# Orion_Ground_Base.net
KiCad netlist of a schematic drawn in EAGLE
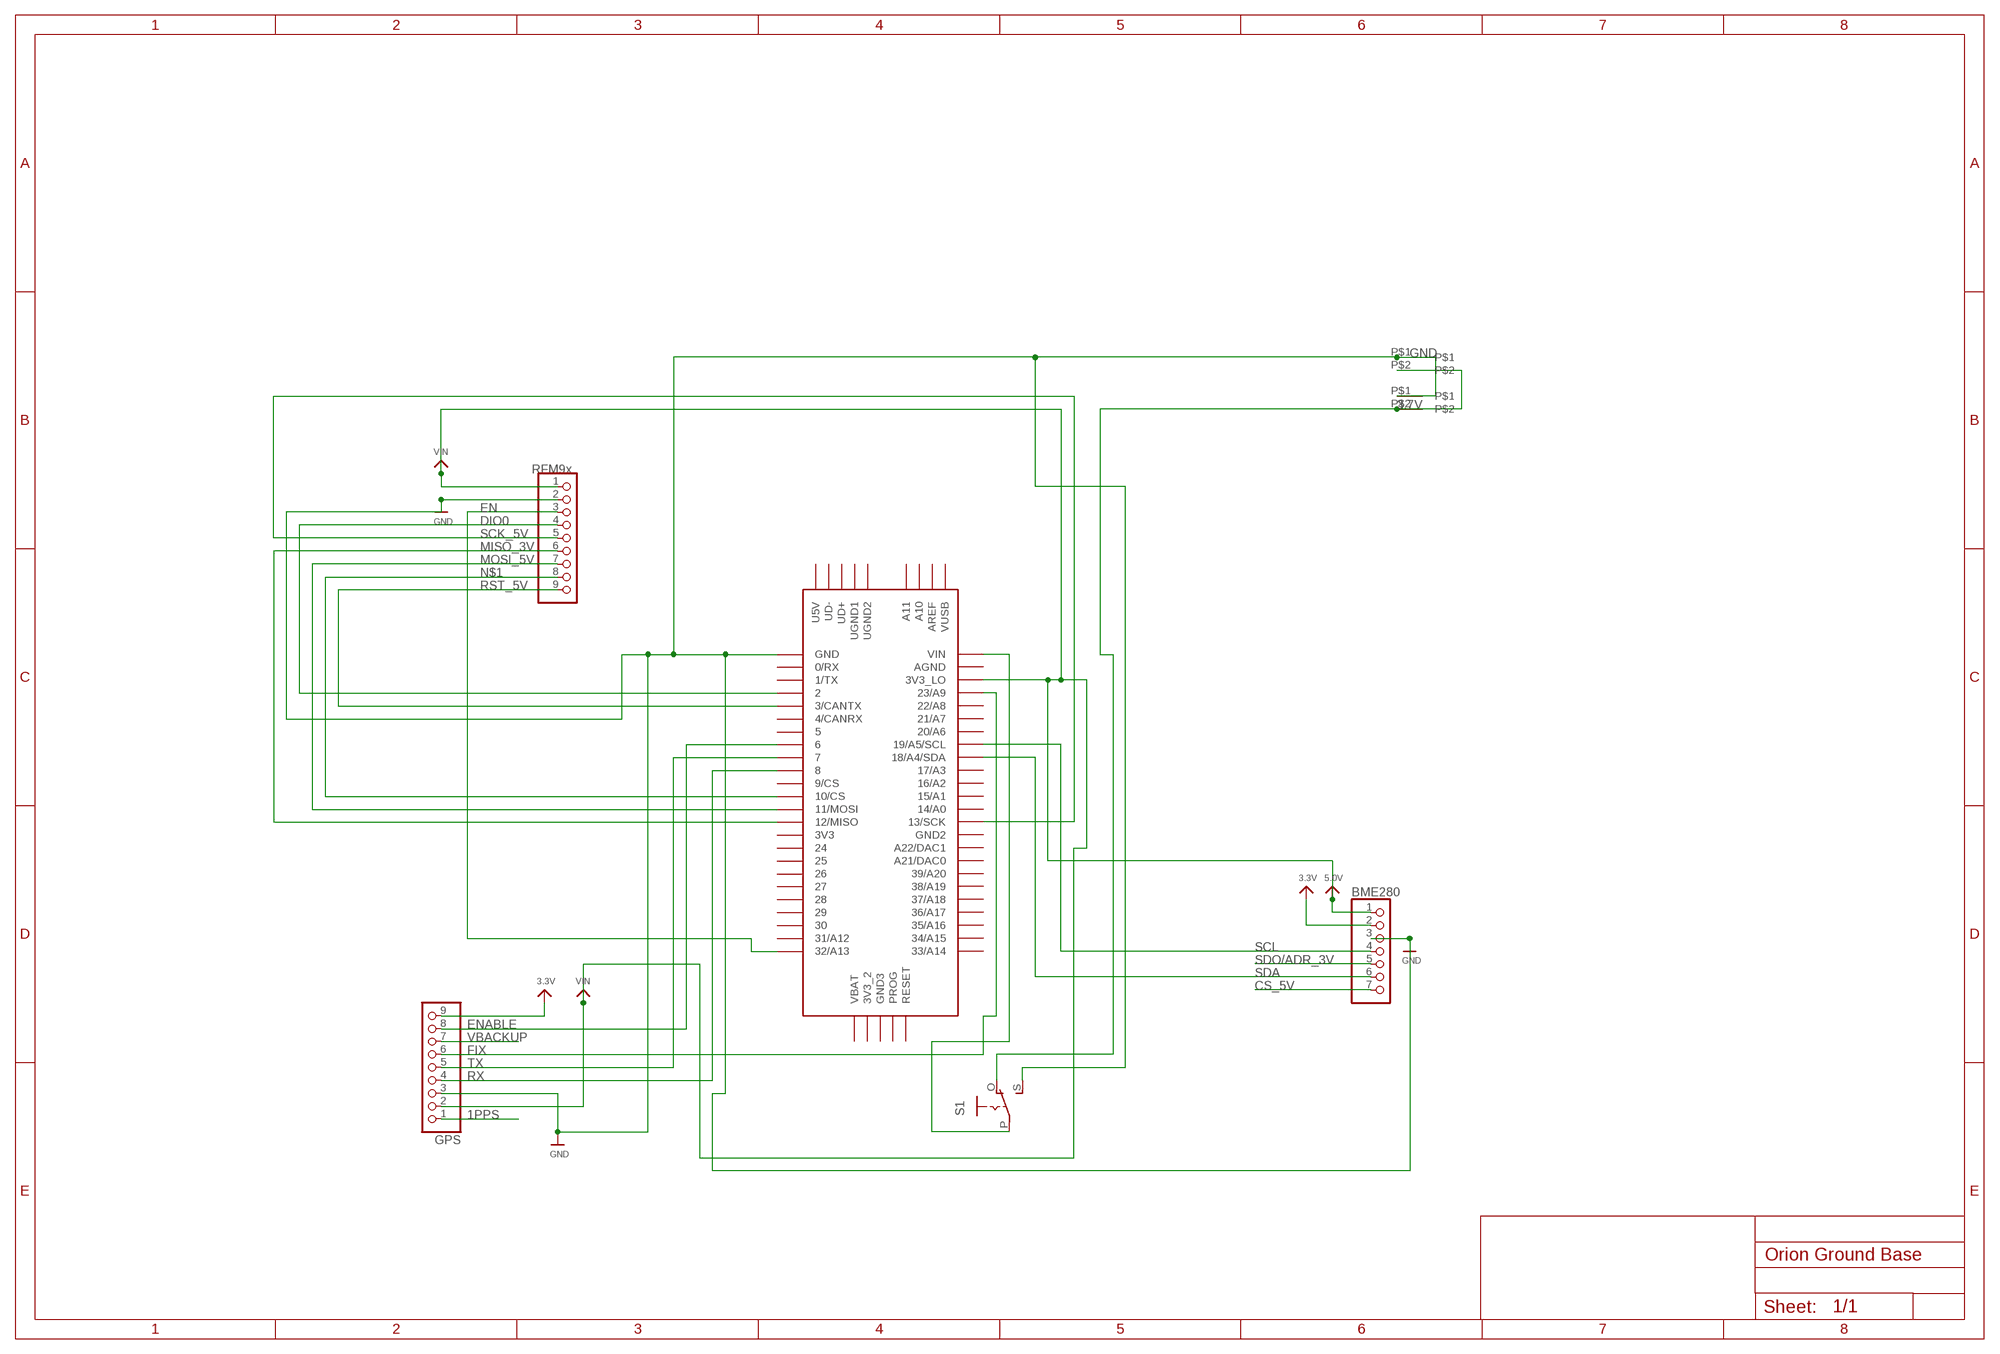
[diagram p0: schematic, sheet 1]

(export (version "E")
  (design (tool "Eeschema 10.0.6"))
  (components
    (comp (ref "BME280")
      (value "HEADER-1X770MIL")
      (footprint "eagle-import:1X07_ROUND_70")
      (libsource (lib "eagle-import") (part "HEADER-1X770MIL"))
    )
    (comp (ref "GPS")
      (value "HEADER-1X970MIL")
      (footprint "eagle-import:1X09_ROUND_70")
      (libsource (lib "eagle-import") (part "HEADER-1X970MIL"))
    )
    (comp (ref "JP3")
      (value "HEADER-1X970MIL")
      (footprint "eagle-import:1X09_ROUND_70")
      (libsource (lib "eagle-import") (part "HEADER-1X970MIL"))
    )
    (comp (ref "S1")
      (value "EG1218S")
      (footprint "eagle-import:EG1218")
      (libsource (lib "eagle-import") (part "EG1218S"))
    )
    (comp (ref "U$1")
      (value "TEENSY_3.5/3.6")
      (footprint "eagle-import:TEENSY_3.5_3.6")
      (libsource (lib "eagle-import") (part "TEENSY_3.5/3.6"))
    )
    (comp (ref "U$7")
      (value "2PINS")
      (footprint "eagle-import:2PINS")
      (libsource (lib "eagle-import") (part "2PINS"))
    )
    (comp (ref "U$8")
      (value "2PINS")
      (footprint "eagle-import:2PINS")
      (libsource (lib "eagle-import") (part "2PINS"))
    )
  )
  (nets
    (net (code "1") (name "/1PPS") (class "Default")
      (node (ref "GPS") (pin "1") (pinfunction "1_1") (pintype "passive"))
    )
    (net (code "2") (name "/CS_5V") (class "Default")
      (node (ref "BME280") (pin "7") (pinfunction "7_7") (pintype "passive"))
    )
    (net (code "3") (name "/DIO0") (class "Default")
      (node (ref "JP3") (pin "4") (pinfunction "4_4") (pintype "passive"))
      (node (ref "U$1") (pin "2") (pinfunction "2_2") (pintype "bidirectional"))
    )
    (net (code "4") (name "/EN") (class "Default")
      (node (ref "JP3") (pin "3") (pinfunction "3_3") (pintype "passive"))
      (node (ref "U$1") (pin "32/A13") (pinfunction "32/A13_32/A13") (pintype "bidirectional"))
    )
    (net (code "5") (name "/ENABLE") (class "Default")
      (node (ref "GPS") (pin "8") (pinfunction "8_8") (pintype "passive"))
      (node (ref "U$1") (pin "6") (pinfunction "6_6") (pintype "bidirectional"))
    )
    (net (code "6") (name "/FIX") (class "Default")
      (node (ref "GPS") (pin "6") (pinfunction "6_6") (pintype "passive"))
      (node (ref "U$1") (pin "23/A9") (pinfunction "23/A9_23/A9") (pintype "bidirectional"))
    )
    (net (code "7") (name "/MISO_3V") (class "Default")
      (node (ref "JP3") (pin "6") (pinfunction "6_6") (pintype "passive"))
      (node (ref "U$1") (pin "12/MISO") (pinfunction "12/MISO_12/MISO") (pintype "bidirectional"))
    )
    (net (code "8") (name "/MOSI_5V") (class "Default")
      (node (ref "JP3") (pin "7") (pinfunction "7_7") (pintype "passive"))
      (node (ref "U$1") (pin "11/MOSI") (pinfunction "11/MOSI_11/MOSI") (pintype "bidirectional"))
    )
    (net (code "9") (name "/N$1") (class "Default")
      (node (ref "JP3") (pin "8") (pinfunction "8_8") (pintype "passive"))
      (node (ref "U$1") (pin "10/CS") (pinfunction "10/CS_10/CS") (pintype "bidirectional"))
    )
    (net (code "10") (name "/RST_5V") (class "Default")
      (node (ref "JP3") (pin "9") (pinfunction "9_9") (pintype "passive"))
      (node (ref "U$1") (pin "3/CANTX") (pinfunction "3/CANTX_3/CANTX") (pintype "bidirectional"))
    )
    (net (code "11") (name "/RX") (class "Default")
      (node (ref "GPS") (pin "4") (pinfunction "4_4") (pintype "passive"))
      (node (ref "U$1") (pin "8") (pinfunction "8_8") (pintype "bidirectional"))
    )
    (net (code "12") (name "/SCK_5V") (class "Default")
      (node (ref "JP3") (pin "5") (pinfunction "5_5") (pintype "passive"))
      (node (ref "U$1") (pin "13/SCK") (pinfunction "13/SCK_13/SCK") (pintype "bidirectional"))
    )
    (net (code "13") (name "/SCL") (class "Default")
      (node (ref "BME280") (pin "4") (pinfunction "4_4") (pintype "passive"))
      (node (ref "U$1") (pin "19/A5/SCL") (pinfunction "19/A5/SCL_19/A5/SCL") (pintype "bidirectional"))
    )
    (net (code "14") (name "/SDA") (class "Default")
      (node (ref "BME280") (pin "6") (pinfunction "6_6") (pintype "passive"))
      (node (ref "U$1") (pin "18/A4/SDA") (pinfunction "18/A4/SDA_18/A4/SDA") (pintype "bidirectional"))
    )
    (net (code "15") (name "/SDO{slash}ADR_3V") (class "Default")
      (node (ref "BME280") (pin "5") (pinfunction "5_5") (pintype "passive"))
    )
    (net (code "16") (name "/TX") (class "Default")
      (node (ref "GPS") (pin "5") (pinfunction "5_5") (pintype "passive"))
      (node (ref "U$1") (pin "7") (pinfunction "7_7") (pintype "bidirectional"))
    )
    (net (code "17") (name "/VBACKUP") (class "Default")
      (node (ref "GPS") (pin "7") (pinfunction "7_7") (pintype "passive"))
    )
    (net (code "18") (name "3.3V") (class "Default")
      (node (ref "BME280") (pin "2") (pinfunction "2_2") (pintype "passive"))
      (node (ref "GPS") (pin "9") (pinfunction "9_9") (pintype "passive"))
    )
    (net (code "19") (name "5.0V") (class "Default")
      (node (ref "BME280") (pin "1") (pinfunction "1_1") (pintype "passive"))
      (node (ref "GPS") (pin "2") (pinfunction "2_2") (pintype "passive"))
      (node (ref "JP3") (pin "1") (pinfunction "1_1") (pintype "passive"))
      (node (ref "U$1") (pin "3V3_LO") (pinfunction "3V3_LO_3V3_LO") (pintype "bidirectional"))
    )
    (net (code "20") (name "GND") (class "Default")
      (node (ref "BME280") (pin "3") (pinfunction "3_3") (pintype "passive"))
      (node (ref "GPS") (pin "3") (pinfunction "3_3") (pintype "passive"))
      (node (ref "JP3") (pin "2") (pinfunction "2_2") (pintype "passive"))
      (node (ref "S1") (pin "S") (pinfunction "S_S") (pintype "passive"))
      (node (ref "U$1") (pin "GND") (pinfunction "GND_GND") (pintype "bidirectional"))
      (node (ref "U$7") (pin "P$1") (pinfunction "P$1_P$1") (pintype "bidirectional"))
      (node (ref "U$8") (pin "P$1") (pinfunction "P$1_P$1") (pintype "bidirectional"))
    )
    (net (code "21") (name "Net-(S1-PadO)") (class "Default")
      (node (ref "S1") (pin "O") (pinfunction "O_O") (pintype "passive"))
      (node (ref "U$7") (pin "P$2") (pinfunction "P$2_P$2") (pintype "bidirectional"))
      (node (ref "U$8") (pin "P$2") (pinfunction "P$2_P$2") (pintype "bidirectional"))
    )
    (net (code "22") (name "Net-(S1-PadP)") (class "Default")
      (node (ref "S1") (pin "P") (pinfunction "P_P") (pintype "passive"))
      (node (ref "U$1") (pin "VIN") (pinfunction "VIN_VIN") (pintype "bidirectional"))
    )
    (net (code "23") (name "unconnected-(U$1-A21{slash}DAC0-Pad21{slash}DAC0)") (class "Default")
      (node (ref "U$1") (pin "21/DAC0") (pinfunction "A21/DAC0_21/DAC0") (pintype "bidirectional"))
    )
    (net (code "24") (name "unconnected-(U$1-Pad0{slash}RX)") (class "Default")
      (node (ref "U$1") (pin "0/RX") (pinfunction "0/RX_0/RX") (pintype "bidirectional"))
    )
    (net (code "25") (name "unconnected-(U$1-Pad1{slash}TX)") (class "Default")
      (node (ref "U$1") (pin "1/TX") (pinfunction "1/TX_1/TX") (pintype "bidirectional"))
    )
    (net (code "26") (name "unconnected-(U$1-Pad3V3)") (class "Default")
      (node (ref "U$1") (pin "3V3") (pinfunction "3V3_3V3") (pintype "bidirectional"))
    )
    (net (code "27") (name "unconnected-(U$1-Pad3V3_2)") (class "Default")
      (node (ref "U$1") (pin "3V3_2") (pinfunction "3V3_2_3V3_2") (pintype "bidirectional"))
    )
    (net (code "28") (name "unconnected-(U$1-Pad4{slash}CANRX)") (class "Default")
      (node (ref "U$1") (pin "4/CANRX") (pinfunction "4/CANRX_4/CANRX") (pintype "bidirectional"))
    )
    (net (code "29") (name "unconnected-(U$1-Pad5)") (class "Default")
      (node (ref "U$1") (pin "5") (pinfunction "5_5") (pintype "bidirectional"))
    )
    (net (code "30") (name "unconnected-(U$1-Pad9{slash}CS)") (class "Default")
      (node (ref "U$1") (pin "9/CS") (pinfunction "9/CS_9/CS") (pintype "bidirectional"))
    )
    (net (code "31") (name "unconnected-(U$1-Pad14{slash}A0)") (class "Default")
      (node (ref "U$1") (pin "14/A0") (pinfunction "14/A0_14/A0") (pintype "bidirectional"))
    )
    (net (code "32") (name "unconnected-(U$1-Pad15{slash}A1)") (class "Default")
      (node (ref "U$1") (pin "15/A1") (pinfunction "15/A1_15/A1") (pintype "bidirectional"))
    )
    (net (code "33") (name "unconnected-(U$1-Pad16{slash}A2)") (class "Default")
      (node (ref "U$1") (pin "16/A2") (pinfunction "16/A2_16/A2") (pintype "bidirectional"))
    )
    (net (code "34") (name "unconnected-(U$1-Pad17{slash}A3)") (class "Default")
      (node (ref "U$1") (pin "17/A3") (pinfunction "17/A3_17/A3") (pintype "bidirectional"))
    )
    (net (code "35") (name "unconnected-(U$1-Pad20{slash}A6)") (class "Default")
      (node (ref "U$1") (pin "20/A6") (pinfunction "20/A6_20/A6") (pintype "bidirectional"))
    )
    (net (code "36") (name "unconnected-(U$1-Pad21{slash}A7)") (class "Default")
      (node (ref "U$1") (pin "21/A7") (pinfunction "21/A7_21/A7") (pintype "bidirectional"))
    )
    (net (code "37") (name "unconnected-(U$1-Pad22{slash}A8)") (class "Default")
      (node (ref "U$1") (pin "22/A8") (pinfunction "22/A8_22/A8") (pintype "bidirectional"))
    )
    (net (code "38") (name "unconnected-(U$1-Pad24)") (class "Default")
      (node (ref "U$1") (pin "24") (pinfunction "24_24") (pintype "bidirectional"))
    )
    (net (code "39") (name "unconnected-(U$1-Pad25)") (class "Default")
      (node (ref "U$1") (pin "25") (pinfunction "25_25") (pintype "bidirectional"))
    )
    (net (code "40") (name "unconnected-(U$1-Pad26)") (class "Default")
      (node (ref "U$1") (pin "26") (pinfunction "26_26") (pintype "bidirectional"))
    )
    (net (code "41") (name "unconnected-(U$1-Pad27)") (class "Default")
      (node (ref "U$1") (pin "27") (pinfunction "27_27") (pintype "bidirectional"))
    )
    (net (code "42") (name "unconnected-(U$1-Pad28)") (class "Default")
      (node (ref "U$1") (pin "28") (pinfunction "28_28") (pintype "bidirectional"))
    )
    (net (code "43") (name "unconnected-(U$1-Pad29)") (class "Default")
      (node (ref "U$1") (pin "29") (pinfunction "29_29") (pintype "bidirectional"))
    )
    (net (code "44") (name "unconnected-(U$1-Pad30)") (class "Default")
      (node (ref "U$1") (pin "30") (pinfunction "30_30") (pintype "bidirectional"))
    )
    (net (code "45") (name "unconnected-(U$1-Pad31{slash}A12)") (class "Default")
      (node (ref "U$1") (pin "31/A12") (pinfunction "31/A12_31/A12") (pintype "bidirectional"))
    )
    (net (code "46") (name "unconnected-(U$1-Pad33{slash}A14)") (class "Default")
      (node (ref "U$1") (pin "33/A14") (pinfunction "33/A14_33/A14") (pintype "bidirectional"))
    )
    (net (code "47") (name "unconnected-(U$1-Pad34{slash}A15)") (class "Default")
      (node (ref "U$1") (pin "34/A15") (pinfunction "34/A15_34/A15") (pintype "bidirectional"))
    )
    (net (code "48") (name "unconnected-(U$1-Pad35{slash}A16)") (class "Default")
      (node (ref "U$1") (pin "35/A16") (pinfunction "35/A16_35/A16") (pintype "bidirectional"))
    )
    (net (code "49") (name "unconnected-(U$1-Pad36{slash}A17)") (class "Default")
      (node (ref "U$1") (pin "36/A17") (pinfunction "36/A17_36/A17") (pintype "bidirectional"))
    )
    (net (code "50") (name "unconnected-(U$1-Pad37{slash}A18)") (class "Default")
      (node (ref "U$1") (pin "37/A18") (pinfunction "37/A18_37/A18") (pintype "bidirectional"))
    )
    (net (code "51") (name "unconnected-(U$1-Pad38{slash}A19)") (class "Default")
      (node (ref "U$1") (pin "38/A19") (pinfunction "38/A19_38/A19") (pintype "bidirectional"))
    )
    (net (code "52") (name "unconnected-(U$1-Pad39{slash}A20)") (class "Default")
      (node (ref "U$1") (pin "39/A20") (pinfunction "39/A20_39/A20") (pintype "bidirectional"))
    )
    (net (code "53") (name "unconnected-(U$1-PadA10)") (class "Default")
      (node (ref "U$1") (pin "A10") (pinfunction "A10_A10") (pintype "bidirectional"))
    )
    (net (code "54") (name "unconnected-(U$1-PadA11)") (class "Default")
      (node (ref "U$1") (pin "A11") (pinfunction "A11_A11") (pintype "bidirectional"))
    )
    (net (code "55") (name "unconnected-(U$1-PadA22{slash}DAC1)") (class "Default")
      (node (ref "U$1") (pin "A22/DAC1") (pinfunction "A22/DAC1_A22/DAC1") (pintype "bidirectional"))
    )
    (net (code "56") (name "unconnected-(U$1-PadAGND)") (class "Default")
      (node (ref "U$1") (pin "AGND") (pinfunction "AGND_AGND") (pintype "bidirectional"))
    )
    (net (code "57") (name "unconnected-(U$1-PadAREF)") (class "Default")
      (node (ref "U$1") (pin "AREF") (pinfunction "AREF_AREF") (pintype "bidirectional"))
    )
    (net (code "58") (name "unconnected-(U$1-PadGND2)") (class "Default")
      (node (ref "U$1") (pin "GND2") (pinfunction "GND2_GND2") (pintype "bidirectional"))
    )
    (net (code "59") (name "unconnected-(U$1-PadGND3)") (class "Default")
      (node (ref "U$1") (pin "GND3") (pinfunction "GND3_GND3") (pintype "bidirectional"))
    )
    (net (code "60") (name "unconnected-(U$1-PadPROG)") (class "Default")
      (node (ref "U$1") (pin "PROG") (pinfunction "PROG_PROG") (pintype "bidirectional"))
    )
    (net (code "61") (name "unconnected-(U$1-PadRESET)") (class "Default")
      (node (ref "U$1") (pin "RESET") (pinfunction "RESET_RESET") (pintype "bidirectional"))
    )
    (net (code "62") (name "unconnected-(U$1-PadU5V)") (class "Default")
      (node (ref "U$1") (pin "U5V") (pinfunction "U5V_U5V") (pintype "bidirectional"))
    )
    (net (code "63") (name "unconnected-(U$1-PadUD+)") (class "Default")
      (node (ref "U$1") (pin "UD+") (pinfunction "UD+_UD+") (pintype "bidirectional"))
    )
    (net (code "64") (name "unconnected-(U$1-PadUD-)") (class "Default")
      (node (ref "U$1") (pin "UD-") (pinfunction "UD-_UD-") (pintype "bidirectional"))
    )
    (net (code "65") (name "unconnected-(U$1-PadUGND1)") (class "Default")
      (node (ref "U$1") (pin "UGND1") (pinfunction "UGND1_UGND1") (pintype "bidirectional"))
    )
    (net (code "66") (name "unconnected-(U$1-PadUGND2)") (class "Default")
      (node (ref "U$1") (pin "UGND2") (pinfunction "UGND2_UGND2") (pintype "bidirectional"))
    )
    (net (code "67") (name "unconnected-(U$1-PadVBAT)") (class "Default")
      (node (ref "U$1") (pin "VBAT") (pinfunction "VBAT_VBAT") (pintype "bidirectional"))
    )
    (net (code "68") (name "unconnected-(U$1-PadVUSB)") (class "Default")
      (node (ref "U$1") (pin "VUSB") (pinfunction "VUSB_VUSB") (pintype "bidirectional"))
    )
  )
)
